# Voltage_meter_Rev1.net
KiCad netlist of a schematic drawn in EAGLE
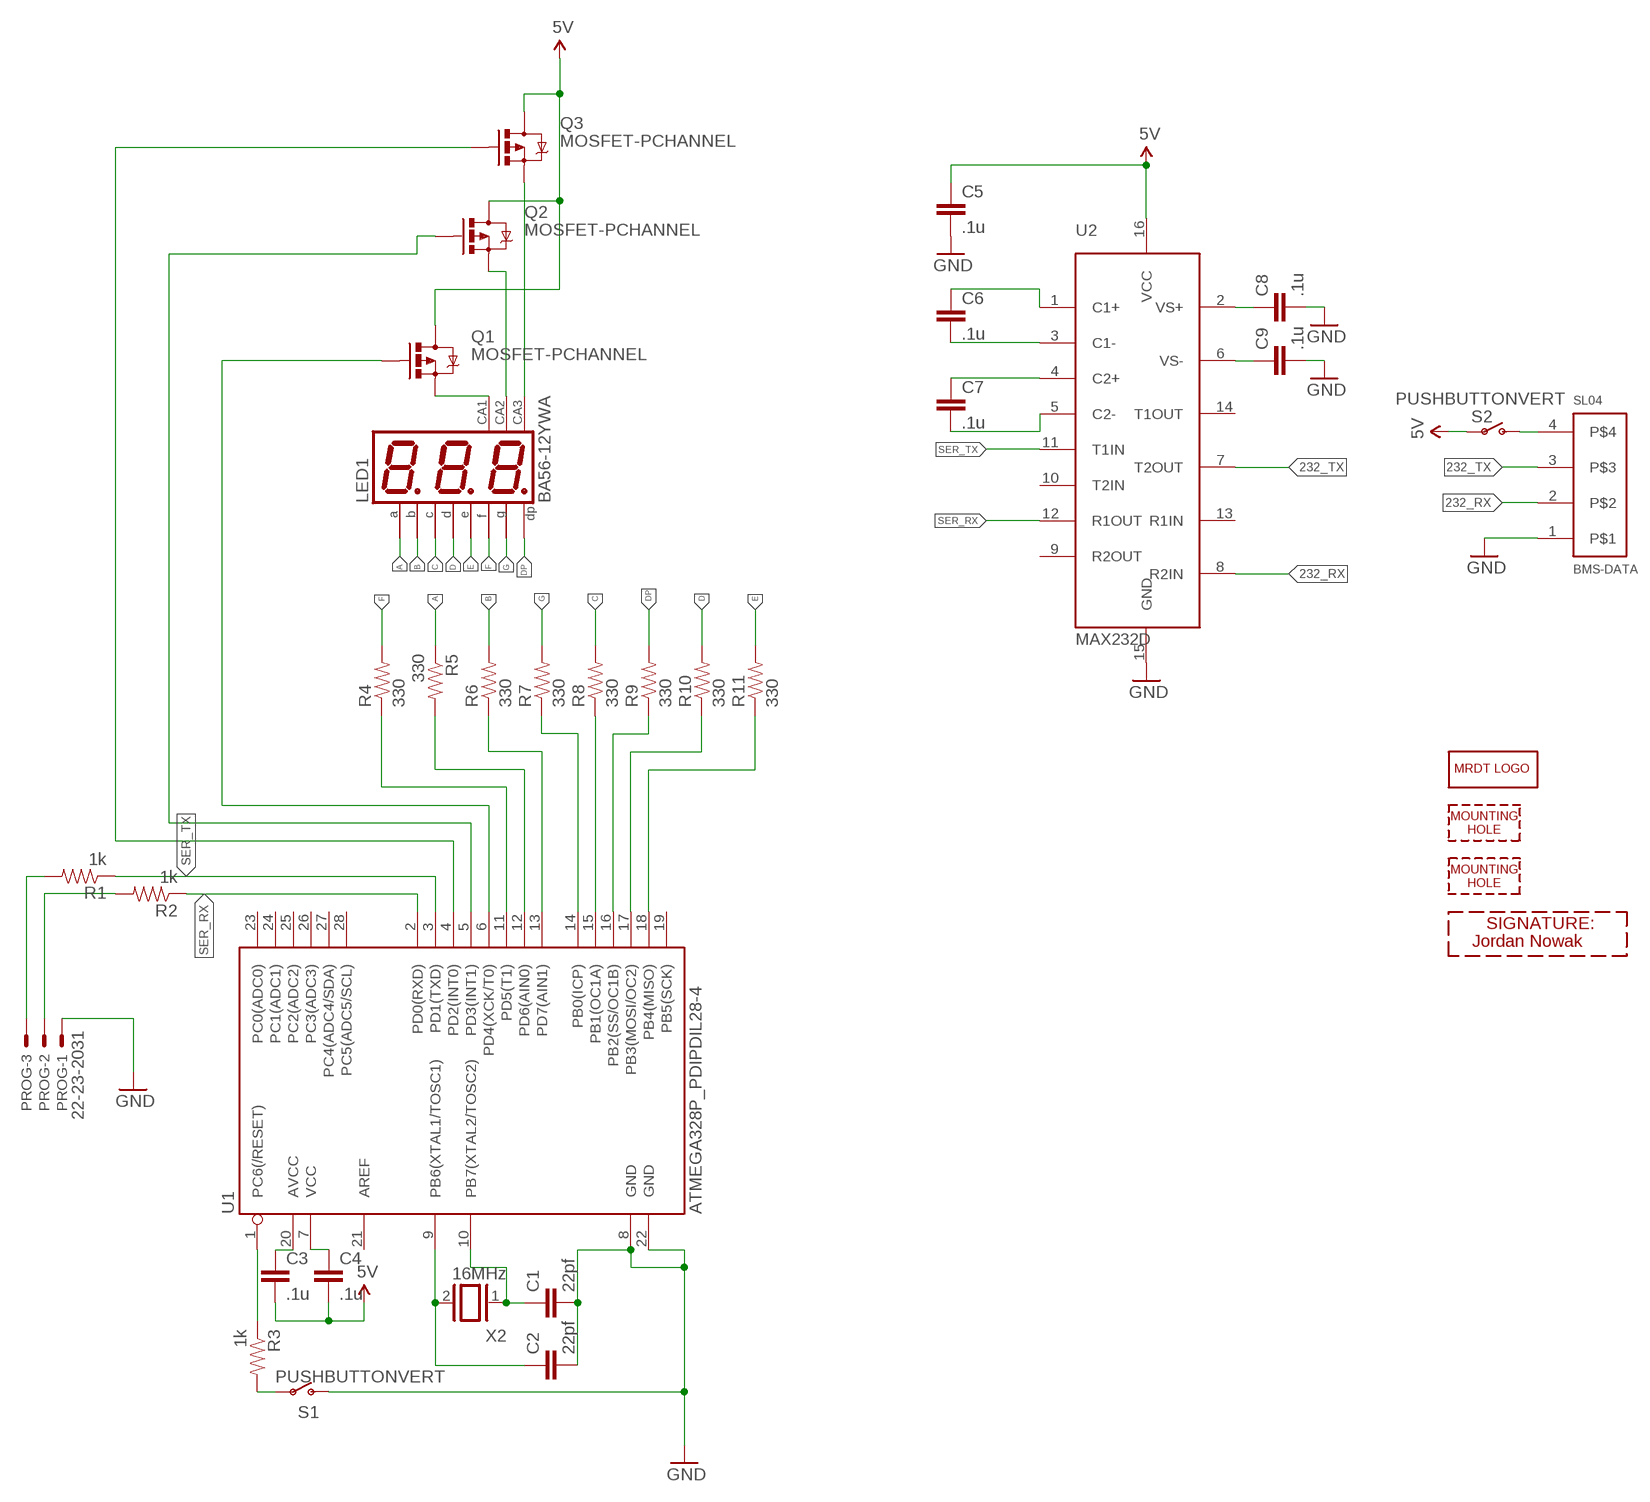
[diagram p0: schematic, sheet 1]

(export (version "E")
  (design (tool "Eeschema 10.0.6"))
  (components
    (comp (ref "BMS-DATA")
      (value "SL04")
      (footprint "eagle-import:MOLEX_SL_04_TH")
      (libsource (lib "eagle-import") (part "SL04"))
    )
    (comp (ref "C1")
      (value "22pf")
      (footprint "eagle-import:0805")
      (libsource (lib "eagle-import") (part "CAP0805"))
    )
    (comp (ref "C2")
      (value "22pf")
      (footprint "eagle-import:0805")
      (libsource (lib "eagle-import") (part "CAP0805"))
    )
    (comp (ref "C3")
      (value ".1u")
      (footprint "eagle-import:0805")
      (libsource (lib "eagle-import") (part "CAP0805"))
    )
    (comp (ref "C4")
      (value ".1u")
      (footprint "eagle-import:0805")
      (libsource (lib "eagle-import") (part "CAP0805"))
    )
    (comp (ref "C5")
      (value ".1u")
      (footprint "eagle-import:0805")
      (libsource (lib "eagle-import") (part "CAP0805"))
    )
    (comp (ref "C6")
      (value ".1u")
      (footprint "eagle-import:0805")
      (libsource (lib "eagle-import") (part "CAP0805"))
    )
    (comp (ref "C7")
      (value ".1u")
      (footprint "eagle-import:0805")
      (libsource (lib "eagle-import") (part "CAP0805"))
    )
    (comp (ref "C8")
      (value ".1u")
      (footprint "eagle-import:0805")
      (libsource (lib "eagle-import") (part "CAP0805"))
    )
    (comp (ref "C9")
      (value ".1u")
      (footprint "eagle-import:0805")
      (libsource (lib "eagle-import") (part "CAP0805"))
    )
    (comp (ref "H1")
      (value "MOUNTING_HOLE#4")
      (footprint "eagle-import:#4_SCREW")
      (libsource (lib "eagle-import") (part "MOUNTING_HOLE#4"))
    )
    (comp (ref "H4")
      (value "MOUNTING_HOLE#4")
      (footprint "eagle-import:#4_SCREW")
      (libsource (lib "eagle-import") (part "MOUNTING_HOLE#4"))
    )
    (comp (ref "LED1")
      (value "BA56-12YWA")
      (footprint "eagle-import:BX56-12")
      (libsource (lib "eagle-import") (part "B?56-12WAAY"))
    )
    (comp (ref "LOGO1")
      (value "MRDT_LOGO")
      (footprint "eagle-import:MRDT_LOGO")
      (libsource (lib "eagle-import") (part "MRDT_LOGO"))
    )
    (comp (ref "PROG")
      (value "22-23-2031")
      (footprint "eagle-import:22-23-2031")
      (fields (field (name "MF") "MOLEX"))
      (libsource (lib "eagle-import") (part "22-23-2031"))
    )
    (comp (ref "Q1")
      (value "MOSFET-PCHANNEL")
      (footprint "eagle-import:SOT23-3")
      (libsource (lib "eagle-import") (part "MOSFET-PCHANNEL"))
    )
    (comp (ref "Q2")
      (value "MOSFET-PCHANNEL")
      (footprint "eagle-import:SOT23-3")
      (libsource (lib "eagle-import") (part "MOSFET-PCHANNEL"))
    )
    (comp (ref "Q3")
      (value "MOSFET-PCHANNEL")
      (footprint "eagle-import:SOT23-3")
      (libsource (lib "eagle-import") (part "MOSFET-PCHANNEL"))
    )
    (comp (ref "R1")
      (value "1k")
      (footprint "eagle-import:0805")
      (libsource (lib "eagle-import") (part "RESISTOR0805-RES"))
    )
    (comp (ref "R2")
      (value "1k")
      (footprint "eagle-import:0805")
      (libsource (lib "eagle-import") (part "RESISTOR0805-RES"))
    )
    (comp (ref "R3")
      (value "1k")
      (footprint "eagle-import:0805")
      (libsource (lib "eagle-import") (part "RESISTOR0805-RES"))
    )
    (comp (ref "R4")
      (value "330")
      (footprint "eagle-import:0805")
      (libsource (lib "eagle-import") (part "RESISTOR0805-RES"))
    )
    (comp (ref "R5")
      (value "330")
      (footprint "eagle-import:0805")
      (libsource (lib "eagle-import") (part "RESISTOR0805-RES"))
    )
    (comp (ref "R6")
      (value "330")
      (footprint "eagle-import:0805")
      (libsource (lib "eagle-import") (part "RESISTOR0805-RES"))
    )
    (comp (ref "R7")
      (value "330")
      (footprint "eagle-import:0805")
      (libsource (lib "eagle-import") (part "RESISTOR0805-RES"))
    )
    (comp (ref "R8")
      (value "330")
      (footprint "eagle-import:0805")
      (libsource (lib "eagle-import") (part "RESISTOR0805-RES"))
    )
    (comp (ref "R9")
      (value "330")
      (footprint "eagle-import:0805")
      (libsource (lib "eagle-import") (part "RESISTOR0805-RES"))
    )
    (comp (ref "R10")
      (value "330")
      (footprint "eagle-import:0805")
      (libsource (lib "eagle-import") (part "RESISTOR0805-RES"))
    )
    (comp (ref "R11")
      (value "330")
      (footprint "eagle-import:0805")
      (libsource (lib "eagle-import") (part "RESISTOR0805-RES"))
    )
    (comp (ref "S1")
      (value "PUSHBUTTONVERT")
      (footprint "eagle-import:APEM-MJTP1243")
      (fields (field (name "PARTNO") "MJTP1243"))
      (libsource (lib "eagle-import") (part "PUSHBUTTONVERT"))
    )
    (comp (ref "S2")
      (value "PUSHBUTTONVERT")
      (footprint "eagle-import:APEM-MJTP1243")
      (fields (field (name "PARTNO") "MJTP1243"))
      (libsource (lib "eagle-import") (part "PUSHBUTTONVERT"))
    )
    (comp (ref "U$1")
      (value "JORDAN-NOWAK")
      (footprint "eagle-import:JORDAN-NOWAK-SIG")
      (libsource (lib "eagle-import") (part "JORDAN-NOWAK"))
    )
    (comp (ref "U1")
      (value "ATMEGA328P_PDIPDIL28-4")
      (footprint "eagle-import:CONN_IC_DIP_SOCKET_28POS")
      (libsource (lib "eagle-import") (part "ATMEGA328P_PDIPDIL28-4"))
    )
    (comp (ref "U2")
      (value "MAX232D")
      (footprint "eagle-import:SOIC16")
      (libsource (lib "eagle-import") (part "MAX232D"))
    )
    (comp (ref "X2")
      (value "16MHz")
      (footprint "eagle-import:QS")
      (libsource (lib "eagle-import") (part "XTAL/S"))
    )
  )
  (nets
    (net (code "1") (name "5V") (class "Default")
      (node (ref "C3") (pin "2") (pinfunction "2_2") (pintype "passive"))
      (node (ref "C4") (pin "2") (pinfunction "2_2") (pintype "passive"))
      (node (ref "C5") (pin "1") (pinfunction "1_1") (pintype "passive"))
      (node (ref "Q1") (pin "3") (pinfunction "D_3") (pintype "passive"))
      (node (ref "Q2") (pin "3") (pinfunction "D_3") (pintype "passive"))
      (node (ref "Q3") (pin "3") (pinfunction "D_3") (pintype "passive"))
      (node (ref "S2") (pin "P$1") (pinfunction "P_P$1") (pintype "passive"))
      (node (ref "U2") (pin "16") (pinfunction "VCC_16") (pintype "bidirectional"))
    )
    (net (code "2") (name "232_RX") (class "Default")
      (node (ref "BMS-DATA") (pin "2") (pinfunction "P$2_2") (pintype "bidirectional"))
      (node (ref "U2") (pin "8") (pinfunction "R2IN_8") (pintype "bidirectional"))
    )
    (net (code "3") (name "232_TX") (class "Default")
      (node (ref "BMS-DATA") (pin "3") (pinfunction "P$3_3") (pintype "bidirectional"))
      (node (ref "U2") (pin "7") (pinfunction "T2OUT_7") (pintype "bidirectional"))
    )
    (net (code "4") (name "A") (class "Default")
      (node (ref "LED1") (pin "11") (pinfunction "A_11") (pintype "passive"))
      (node (ref "R5") (pin "1") (pinfunction "1_1") (pintype "passive"))
    )
    (net (code "5") (name "B") (class "Default")
      (node (ref "LED1") (pin "7") (pinfunction "B_7") (pintype "passive"))
      (node (ref "R6") (pin "2") (pinfunction "2_2") (pintype "passive"))
    )
    (net (code "6") (name "C") (class "Default")
      (node (ref "LED1") (pin "4") (pinfunction "C_4") (pintype "passive"))
      (node (ref "R8") (pin "2") (pinfunction "2_2") (pintype "passive"))
    )
    (net (code "7") (name "D") (class "Default")
      (node (ref "LED1") (pin "2") (pinfunction "D_2") (pintype "passive"))
      (node (ref "R10") (pin "2") (pinfunction "2_2") (pintype "passive"))
    )
    (net (code "8") (name "DP") (class "Default")
      (node (ref "LED1") (pin "3") (pinfunction "DP_3") (pintype "passive"))
      (node (ref "R9") (pin "2") (pinfunction "2_2") (pintype "passive"))
    )
    (net (code "9") (name "E") (class "Default")
      (node (ref "LED1") (pin "1") (pinfunction "E_1") (pintype "passive"))
      (node (ref "R11") (pin "2") (pinfunction "2_2") (pintype "passive"))
    )
    (net (code "10") (name "F") (class "Default")
      (node (ref "LED1") (pin "10") (pinfunction "F_10") (pintype "passive"))
      (node (ref "R4") (pin "2") (pinfunction "2_2") (pintype "passive"))
    )
    (net (code "11") (name "G") (class "Default")
      (node (ref "LED1") (pin "5") (pinfunction "G_5") (pintype "passive"))
      (node (ref "R7") (pin "2") (pinfunction "2_2") (pintype "passive"))
    )
    (net (code "12") (name "GND") (class "Default")
      (node (ref "BMS-DATA") (pin "1") (pinfunction "P$1_1") (pintype "bidirectional"))
      (node (ref "C1") (pin "2") (pinfunction "2_2") (pintype "passive"))
      (node (ref "C2") (pin "2") (pinfunction "2_2") (pintype "passive"))
      (node (ref "C5") (pin "2") (pinfunction "2_2") (pintype "passive"))
      (node (ref "C8") (pin "2") (pinfunction "2_2") (pintype "passive"))
      (node (ref "C9") (pin "2") (pinfunction "2_2") (pintype "passive"))
      (node (ref "PROG") (pin "1") (pinfunction "S_1") (pintype "passive"))
      (node (ref "S1") (pin "P$2") (pinfunction "S_P$2") (pintype "passive"))
      (node (ref "U1") (pin "22") (pinfunction "GND_22") (pintype "bidirectional"))
      (node (ref "U1") (pin "8") (pinfunction "GND_8") (pintype "bidirectional"))
      (node (ref "U2") (pin "15") (pinfunction "GND_15") (pintype "bidirectional"))
    )
    (net (code "13") (name "Net-(BMS-DATA-P$4)") (class "Default")
      (node (ref "BMS-DATA") (pin "4") (pinfunction "P$4_4") (pintype "bidirectional"))
      (node (ref "S2") (pin "P$2") (pinfunction "S_P$2") (pintype "passive"))
    )
    (net (code "14") (name "Net-(PROGB-S)") (class "Default")
      (node (ref "PROG") (pin "2") (pinfunction "S_2") (pintype "passive"))
      (node (ref "R2") (pin "2") (pinfunction "2_2") (pintype "passive"))
    )
    (net (code "15") (name "Net-(PROGC-S)") (class "Default")
      (node (ref "PROG") (pin "3") (pinfunction "S_3") (pintype "passive"))
      (node (ref "R1") (pin "2") (pinfunction "2_2") (pintype "passive"))
    )
    (net (code "16") (name "Net-(Q1-G)") (class "Default")
      (node (ref "Q1") (pin "1") (pinfunction "G_1") (pintype "passive"))
      (node (ref "U1") (pin "6") (pinfunction "PD4(XCK/T0)_6") (pintype "bidirectional"))
    )
    (net (code "17") (name "Net-(Q1-S)") (class "Default")
      (node (ref "LED1") (pin "12") (pinfunction "CA_12") (pintype "passive"))
      (node (ref "Q1") (pin "2") (pinfunction "S_2") (pintype "passive"))
    )
    (net (code "18") (name "Net-(Q2-G)") (class "Default")
      (node (ref "Q2") (pin "1") (pinfunction "G_1") (pintype "passive"))
      (node (ref "U1") (pin "5") (pinfunction "PD3(INT1)_5") (pintype "bidirectional"))
    )
    (net (code "19") (name "Net-(Q2-S)") (class "Default")
      (node (ref "LED1") (pin "9") (pinfunction "CA_9") (pintype "passive"))
      (node (ref "Q2") (pin "2") (pinfunction "S_2") (pintype "passive"))
    )
    (net (code "20") (name "Net-(Q3-G)") (class "Default")
      (node (ref "Q3") (pin "1") (pinfunction "G_1") (pintype "passive"))
      (node (ref "U1") (pin "4") (pinfunction "PD2(INT0)_4") (pintype "bidirectional"))
    )
    (net (code "21") (name "Net-(Q3-S)") (class "Default")
      (node (ref "LED1") (pin "8") (pinfunction "CA_8") (pintype "passive"))
      (node (ref "Q3") (pin "2") (pinfunction "S_2") (pintype "passive"))
    )
    (net (code "22") (name "Net-(S1-P)") (class "Default")
      (node (ref "R3") (pin "2") (pinfunction "2_2") (pintype "passive"))
      (node (ref "S1") (pin "P$1") (pinfunction "P_P$1") (pintype "passive"))
    )
    (net (code "23") (name "Net-(U1-AVCC)") (class "Default")
      (node (ref "C3") (pin "1") (pinfunction "1_1") (pintype "passive"))
      (node (ref "U1") (pin "20") (pinfunction "AVCC_20") (pintype "bidirectional"))
    )
    (net (code "24") (name "Net-(U1-PB0(ICP))") (class "Default")
      (node (ref "R7") (pin "1") (pinfunction "1_1") (pintype "passive"))
      (node (ref "U1") (pin "14") (pinfunction "PB0(ICP)_14") (pintype "bidirectional"))
    )
    (net (code "25") (name "Net-(U1-PB1(OC1A))") (class "Default")
      (node (ref "R8") (pin "1") (pinfunction "1_1") (pintype "passive"))
      (node (ref "U1") (pin "15") (pinfunction "PB1(OC1A)_15") (pintype "bidirectional"))
    )
    (net (code "26") (name "Net-(U1-PB2(SS{slash}OC1B))") (class "Default")
      (node (ref "R9") (pin "1") (pinfunction "1_1") (pintype "passive"))
      (node (ref "U1") (pin "16") (pinfunction "PB2(SS/OC1B)_16") (pintype "bidirectional"))
    )
    (net (code "27") (name "Net-(U1-PB3(MOSI{slash}OC2))") (class "Default")
      (node (ref "R10") (pin "1") (pinfunction "1_1") (pintype "passive"))
      (node (ref "U1") (pin "17") (pinfunction "PB3(MOSI/OC2)_17") (pintype "bidirectional"))
    )
    (net (code "28") (name "Net-(U1-PB4(MISO))") (class "Default")
      (node (ref "R11") (pin "1") (pinfunction "1_1") (pintype "passive"))
      (node (ref "U1") (pin "18") (pinfunction "PB4(MISO)_18") (pintype "bidirectional"))
    )
    (net (code "29") (name "Net-(U1-PB6(XTAL1{slash}TOSC1))") (class "Default")
      (node (ref "C2") (pin "1") (pinfunction "1_1") (pintype "passive"))
      (node (ref "U1") (pin "9") (pinfunction "PB6(XTAL1/TOSC1)_9") (pintype "bidirectional"))
      (node (ref "X2") (pin "2") (pinfunction "2_2") (pintype "passive"))
    )
    (net (code "30") (name "Net-(U1-PB7(XTAL2{slash}TOSC2))") (class "Default")
      (node (ref "C1") (pin "1") (pinfunction "1_1") (pintype "passive"))
      (node (ref "U1") (pin "10") (pinfunction "PB7(XTAL2/TOSC2)_10") (pintype "bidirectional"))
      (node (ref "X2") (pin "1") (pinfunction "1_1") (pintype "passive"))
    )
    (net (code "31") (name "Net-(U1-PC6({slash}RESET))") (class "Default")
      (node (ref "R3") (pin "1") (pinfunction "1_1") (pintype "passive"))
      (node (ref "U1") (pin "1") (pinfunction "PC6(/RESET)_1") (pintype "bidirectional"))
    )
    (net (code "32") (name "Net-(U1-PD5(T1))") (class "Default")
      (node (ref "R4") (pin "1") (pinfunction "1_1") (pintype "passive"))
      (node (ref "U1") (pin "11") (pinfunction "PD5(T1)_11") (pintype "bidirectional"))
    )
    (net (code "33") (name "Net-(U1-PD6(AIN0))") (class "Default")
      (node (ref "R5") (pin "2") (pinfunction "2_2") (pintype "passive"))
      (node (ref "U1") (pin "12") (pinfunction "PD6(AIN0)_12") (pintype "bidirectional"))
    )
    (net (code "34") (name "Net-(U1-PD7(AIN1))") (class "Default")
      (node (ref "R6") (pin "1") (pinfunction "1_1") (pintype "passive"))
      (node (ref "U1") (pin "13") (pinfunction "PD7(AIN1)_13") (pintype "bidirectional"))
    )
    (net (code "35") (name "Net-(U1-VCC)") (class "Default")
      (node (ref "C4") (pin "1") (pinfunction "1_1") (pintype "passive"))
      (node (ref "U1") (pin "7") (pinfunction "VCC_7") (pintype "bidirectional"))
    )
    (net (code "36") (name "Net-(U2-C1+)") (class "Default")
      (node (ref "C6") (pin "1") (pinfunction "1_1") (pintype "passive"))
      (node (ref "U2") (pin "1") (pinfunction "C1+_1") (pintype "bidirectional"))
    )
    (net (code "37") (name "Net-(U2-C1-)") (class "Default")
      (node (ref "C6") (pin "2") (pinfunction "2_2") (pintype "passive"))
      (node (ref "U2") (pin "3") (pinfunction "C1-_3") (pintype "bidirectional"))
    )
    (net (code "38") (name "Net-(U2-C2+)") (class "Default")
      (node (ref "C7") (pin "1") (pinfunction "1_1") (pintype "passive"))
      (node (ref "U2") (pin "4") (pinfunction "C2+_4") (pintype "bidirectional"))
    )
    (net (code "39") (name "Net-(U2-C2-)") (class "Default")
      (node (ref "C7") (pin "2") (pinfunction "2_2") (pintype "passive"))
      (node (ref "U2") (pin "5") (pinfunction "C2-_5") (pintype "bidirectional"))
    )
    (net (code "40") (name "Net-(U2-VS+)") (class "Default")
      (node (ref "C8") (pin "1") (pinfunction "1_1") (pintype "passive"))
      (node (ref "U2") (pin "2") (pinfunction "VS+_2") (pintype "bidirectional"))
    )
    (net (code "41") (name "Net-(U2-VS-)") (class "Default")
      (node (ref "C9") (pin "1") (pinfunction "1_1") (pintype "passive"))
      (node (ref "U2") (pin "6") (pinfunction "VS-_6") (pintype "bidirectional"))
    )
    (net (code "42") (name "SER_RX") (class "Default")
      (node (ref "R2") (pin "1") (pinfunction "1_1") (pintype "passive"))
      (node (ref "U1") (pin "2") (pinfunction "PD0(RXD)_2") (pintype "bidirectional"))
      (node (ref "U2") (pin "12") (pinfunction "R1OUT_12") (pintype "bidirectional"))
    )
    (net (code "43") (name "SER_TX") (class "Default")
      (node (ref "R1") (pin "1") (pinfunction "1_1") (pintype "passive"))
      (node (ref "U1") (pin "3") (pinfunction "PD1(TXD)_3") (pintype "bidirectional"))
      (node (ref "U2") (pin "11") (pinfunction "T1IN_11") (pintype "bidirectional"))
    )
    (net (code "44") (name "unconnected-(U1-AREF-Pad21)") (class "Default")
      (node (ref "U1") (pin "21") (pinfunction "AREF_21") (pintype "bidirectional"))
    )
    (net (code "45") (name "unconnected-(U1-PB5(SCK)-Pad19)") (class "Default")
      (node (ref "U1") (pin "19") (pinfunction "PB5(SCK)_19") (pintype "bidirectional"))
    )
    (net (code "46") (name "unconnected-(U1-PC0(ADC0)-Pad23)") (class "Default")
      (node (ref "U1") (pin "23") (pinfunction "PC0(ADC0)_23") (pintype "bidirectional"))
    )
    (net (code "47") (name "unconnected-(U1-PC1(ADC1)-Pad24)") (class "Default")
      (node (ref "U1") (pin "24") (pinfunction "PC1(ADC1)_24") (pintype "bidirectional"))
    )
    (net (code "48") (name "unconnected-(U1-PC2(ADC2)-Pad25)") (class "Default")
      (node (ref "U1") (pin "25") (pinfunction "PC2(ADC2)_25") (pintype "bidirectional"))
    )
    (net (code "49") (name "unconnected-(U1-PC3(ADC3)-Pad26)") (class "Default")
      (node (ref "U1") (pin "26") (pinfunction "PC3(ADC3)_26") (pintype "bidirectional"))
    )
    (net (code "50") (name "unconnected-(U1-PC4(ADC4{slash}SDA)-Pad27)") (class "Default")
      (node (ref "U1") (pin "27") (pinfunction "PC4(ADC4/SDA)_27") (pintype "bidirectional"))
    )
    (net (code "51") (name "unconnected-(U1-PC5(ADC5{slash}SCL)-Pad28)") (class "Default")
      (node (ref "U1") (pin "28") (pinfunction "PC5(ADC5/SCL)_28") (pintype "bidirectional"))
    )
    (net (code "52") (name "unconnected-(U2-R1IN-Pad13)") (class "Default")
      (node (ref "U2") (pin "13") (pinfunction "R1IN_13") (pintype "bidirectional"))
    )
    (net (code "53") (name "unconnected-(U2-R2OUT-Pad9)") (class "Default")
      (node (ref "U2") (pin "9") (pinfunction "R2OUT_9") (pintype "bidirectional"))
    )
    (net (code "54") (name "unconnected-(U2-T1OUT-Pad14)") (class "Default")
      (node (ref "U2") (pin "14") (pinfunction "T1OUT_14") (pintype "bidirectional"))
    )
    (net (code "55") (name "unconnected-(U2-T2IN-Pad10)") (class "Default")
      (node (ref "U2") (pin "10") (pinfunction "T2IN_10") (pintype "bidirectional"))
    )
  )
)
